# HEADERS_POWER.net
KiCad netlist of a schematic drawn in Altium Designer
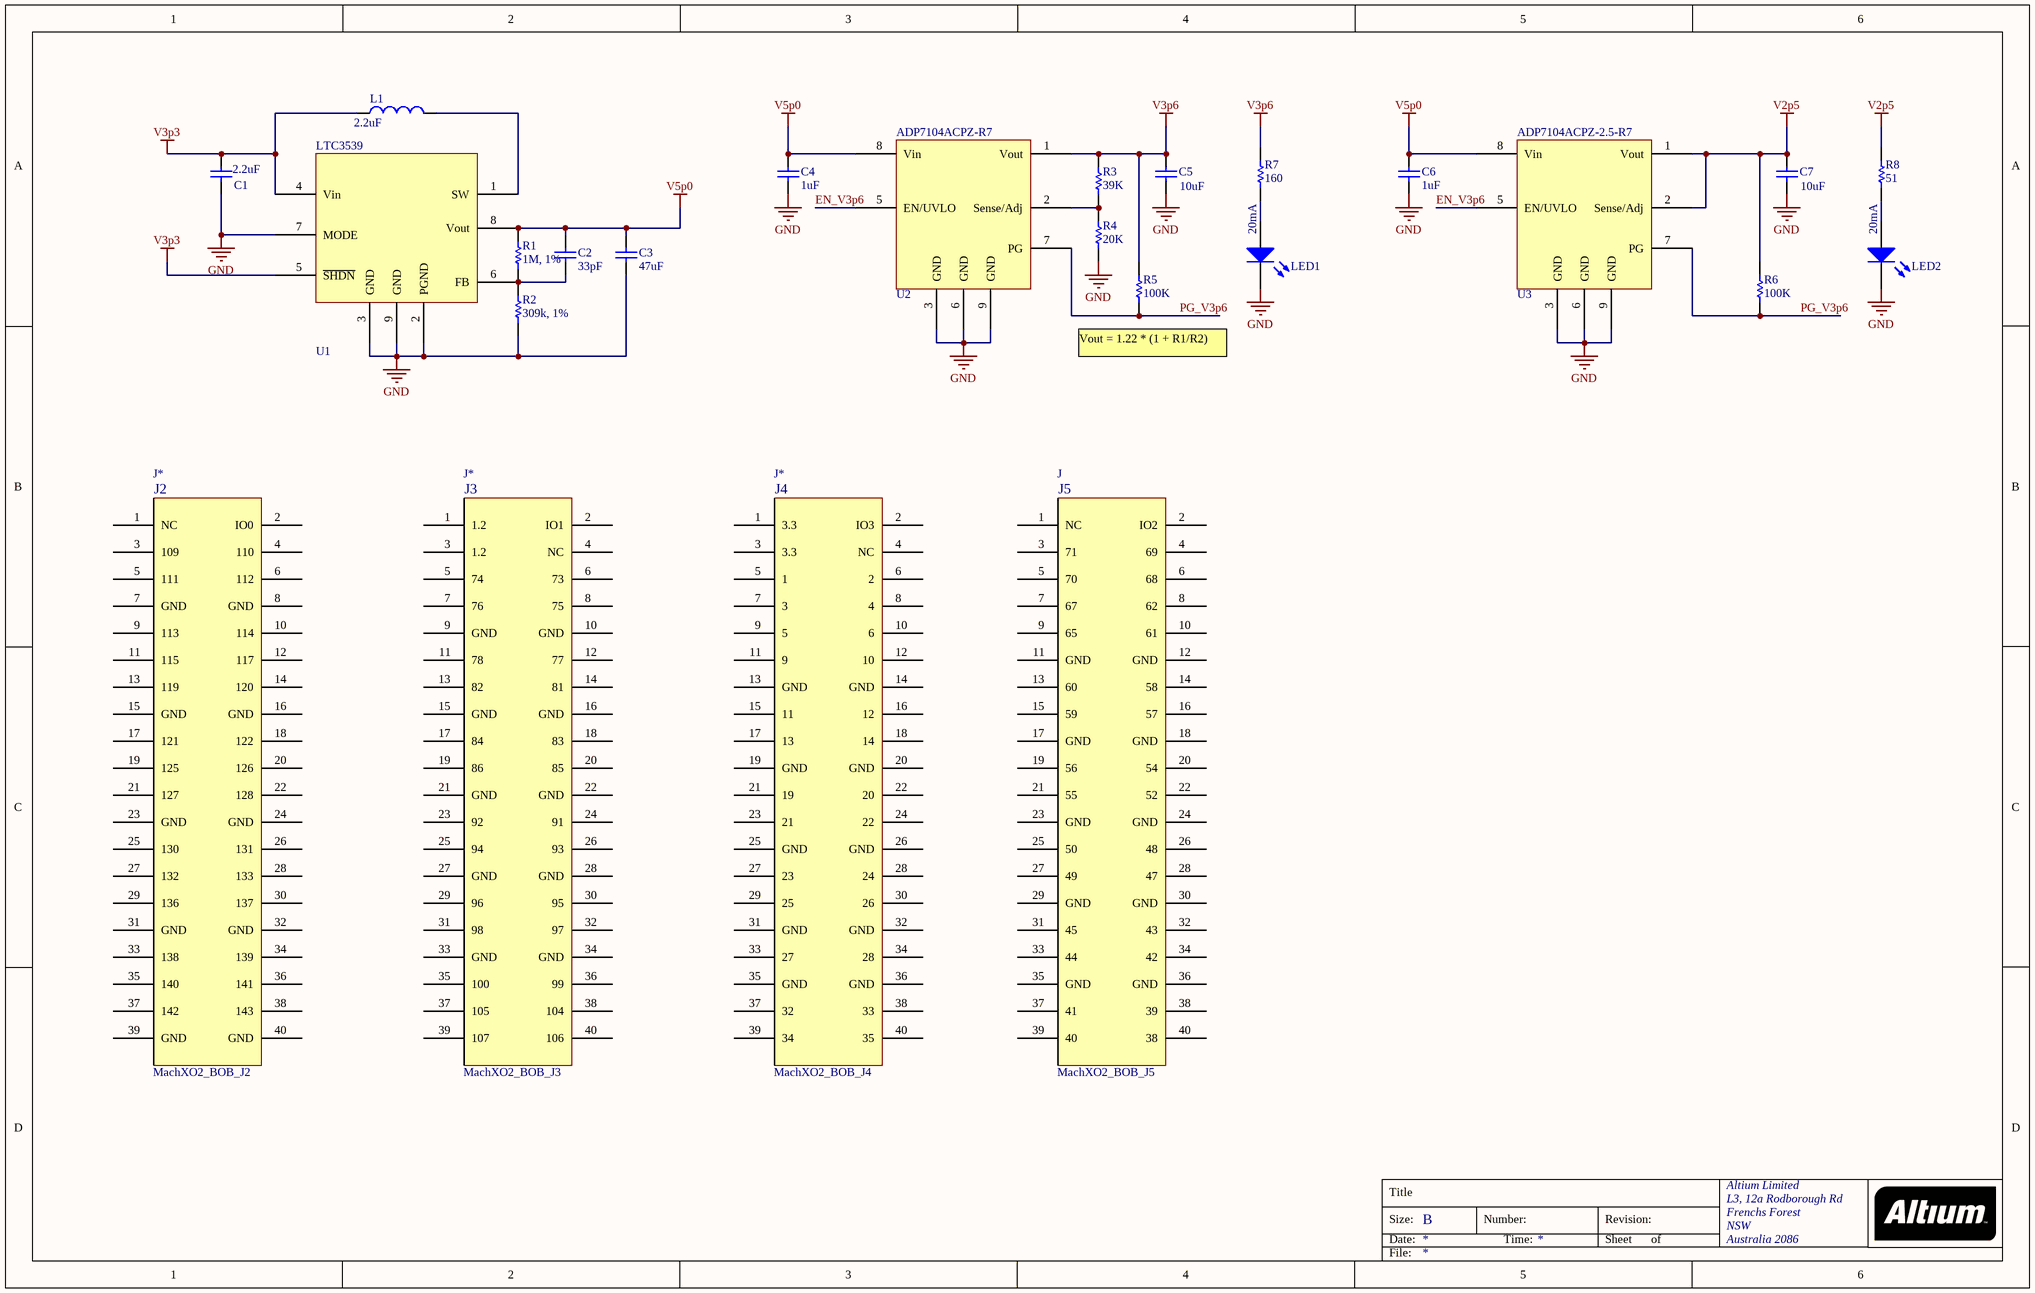
[diagram p0: HEADERS & POWER.SchDoc]

(export (version "E")
  (design (tool "Eeschema 10.0.6"))
  (components
    (comp (ref "C1")
      (value "2.2uF")
      (footprint "CAPC1206(3216)170_N")
      (fields (field (name "Comment") "587-1329-2-ND"))
      (libsource (lib "Components") (part "CAP, 1206, 2.2uF"))
    )
    (comp (ref "C2")
      (value "33pF")
      (footprint "CAPC01005(0402)22_N")
      (fields (field (name "Comment") "CAP, 0402, 33pF"))
      (libsource (lib "Components") (part "CAP, 0402, 33pF"))
    )
    (comp (ref "C3")
      (value "47uF")
      (footprint "CAPC1206(3216)170_N")
      (fields (field (name "Comment") "CAP, 1206, 47uF"))
      (libsource (lib "Components") (part "CAP, 1206, 47uF"))
    )
    (comp (ref "C4")
      (value "1uF")
      (footprint "CAPC01005(0402)22_N")
      (fields (field (name "Comment") "CAP, 0402, 1uF"))
      (libsource (lib "Components") (part "CAP, 0402, 1uF"))
    )
    (comp (ref "C5")
      (value "10uF")
      (footprint "CAPC0805(2012)130_N")
      (fields (field (name "Comment") "CAP, 0805, 10uF"))
      (libsource (lib "Components") (part "CAP, 0805, 10uF"))
    )
    (comp (ref "C6")
      (value "1uF")
      (footprint "CAPC01005(0402)22_N")
      (fields (field (name "Comment") "CAP, 0402, 1uF"))
      (libsource (lib "Components") (part "CAP, 0402, 1uF"))
    )
    (comp (ref "C7")
      (value "10uF")
      (footprint "CAPC0805(2012)130_N")
      (fields (field (name "Comment") "CAP, 0805, 10uF"))
      (libsource (lib "Components") (part "CAP, 0805, 10uF"))
    )
    (comp (ref "J")
      (value "MachXO2_BOB_J5")
      (footprint "RECEPTACLE_25.4MM_20X2")
      (libsource (lib "Components") (part "MachXO2_BOB_J5"))
    )
    (comp (ref "J*")
      (value "MachXO2_BOB_J2")
      (footprint "RECEPTACLE_25.4MM_20X2")
      (libsource (lib "Components") (part "MachXO2_BOB_J2"))
    )
    (comp (ref "L1")
      (value "2.2uF")
      (footprint "INDUCTOR, SMD, TDK")
      (fields (field (name "Comment") "INDUCTOR, SMD, 2.2uF"))
      (libsource (lib "Components") (part "INDUCTOR, SMD, 2.2uF"))
    )
    (comp (ref "LED1")
      (value "LED, GREEN, 0603, LITE-ON")
      (footprint "0603, LED")
      (libsource (lib "Components") (part "LED, GREEN, 0603, LITE-ON"))
    )
    (comp (ref "LED2")
      (value "LED, GREEN, 0603, LITE-ON")
      (footprint "0603, LED")
      (libsource (lib "Components") (part "LED, GREEN, 0603, LITE-ON"))
    )
    (comp (ref "R1")
      (value "1M, 1%")
      (footprint "RESC0402(1005)_N")
      (fields (field (name "Comment") "RES, 0402, 1M, 1%"))
      (libsource (lib "Components") (part "RES, 0402, 1M, 1%"))
    )
    (comp (ref "R2")
      (value "309k, 1%")
      (footprint "RESC0402(1005)_N")
      (fields (field (name "Comment") "RES, 0402, 309k, 1%"))
      (libsource (lib "Components") (part "RES, 0402, 309k, 1%"))
    )
    (comp (ref "R3")
      (value "39K")
      (footprint "RES, 0603")
      (description "Resistor, 0603, 1/10W, 39K ohm")
      (fields
        (field (name "MANUFACTURER") "Panasonic Electronic Components")
        (field (name "MANUFACTURER PART NUMBER") "ERJ-3EKF3902V")
      )
      (libsource (lib "Resistors0603") (part "RES_0603_39K"))
    )
    (comp (ref "R4")
      (value "20K")
      (footprint "RES, 0603")
      (description "Resistor, 0603, 1/10W, 20K ohm")
      (fields
        (field (name "MANUFACTURER") "Panasonic Electronic Components")
        (field (name "MANUFACTURER PART NUMBER") "ERJ-3EKF2002V")
      )
      (libsource (lib "Resistors0603") (part "RES_0603_20K"))
    )
    (comp (ref "R5")
      (value "100K")
      (footprint "RES, 0603")
      (description "Resistor, 0603, 1/10W, 100K ohm")
      (fields
        (field (name "MANUFACTURER") "Panasonic Electronic Components")
        (field (name "MANUFACTURER PART NUMBER") "ERJ-3EKF1003V")
      )
      (libsource (lib "Resistors0603") (part "RES_0603_100K"))
    )
    (comp (ref "R6")
      (value "100K")
      (footprint "RES, 0603")
      (description "Resistor, 0603, 1/10W, 100K ohm")
      (fields
        (field (name "MANUFACTURER") "Panasonic Electronic Components")
        (field (name "MANUFACTURER PART NUMBER") "ERJ-3EKF1003V")
      )
      (libsource (lib "Resistors0603") (part "RES_0603_100K"))
    )
    (comp (ref "R7")
      (value "160")
      (footprint "RESC1005X04N")
      (description "Resistor, 0402, 1/10W, 160 ohm")
      (fields
        (field (name "MANUFACTURER") "Panasonic Electronic Components")
        (field (name "MANUFACTURER PART NUMBER") "ERJ-2RKF1600X")
      )
      (libsource (lib "Resistors0402") (part "RES_0402_160"))
    )
    (comp (ref "R8")
      (value "51")
      (footprint "RESC1005X04N")
      (description "Resistor, 0402, 1/10W, 51 ohm")
      (fields
        (field (name "MANUFACTURER") "Panasonic Electronic Components")
        (field (name "MANUFACTURER PART NUMBER") "ERJ-2RKF51R0X")
      )
      (libsource (lib "Resistors0402") (part "RES_0402_51"))
    )
    (comp (ref "U1")
      (value "LTC3539")
      (footprint "QFN45P300X200X80-8N")
      (libsource (lib "Components") (part "LTC3539"))
    )
    (comp (ref "U2")
      (value "ADP7104ACPZ-R7")
      (footprint "QFN50P300X300X75-8N")
      (description "Adjustable Voltage Regulator")
      (libsource (lib "Components") (part "ADP7104ACPZ-R7"))
    )
    (comp (ref "U3")
      (value "ADP7104ACPZ-2.5-R7")
      (footprint "QFN50P300X300X75-8N")
      (description "2.5V Voltage Regulator")
      (libsource (lib "Components") (part "ADP7104ACPZ-2.5-R7"))
    )
  )
  (nets
    (net (code "1") (name "/EN_V3p6") (class "Default")
      (node (ref "U2") (pin "5") (pinfunction "EN/UVLO_5") (pintype "passive"))
      (node (ref "U3") (pin "5") (pinfunction "EN/UVLO_5") (pintype "passive"))
    )
    (net (code "2") (name "/PG_V3p6") (class "Default")
      (node (ref "R5") (pin "1") (pinfunction "1_1") (pintype "passive"))
      (node (ref "R6") (pin "1") (pinfunction "1_1") (pintype "passive"))
      (node (ref "U2") (pin "7") (pinfunction "PG_7") (pintype "passive"))
      (node (ref "U3") (pin "7") (pinfunction "PG_7") (pintype "passive"))
    )
    (net (code "3") (name "GND") (class "Default")
      (node (ref "C1") (pin "1") (pinfunction "1_1") (pintype "passive"))
      (node (ref "C3") (pin "1") (pinfunction "1_1") (pintype "passive"))
      (node (ref "C4") (pin "1") (pinfunction "1_1") (pintype "passive"))
      (node (ref "C5") (pin "1") (pinfunction "1_1") (pintype "passive"))
      (node (ref "C6") (pin "1") (pinfunction "1_1") (pintype "passive"))
      (node (ref "C7") (pin "1") (pinfunction "1_1") (pintype "passive"))
      (node (ref "LED1") (pin "1") (pinfunction "C_1") (pintype "passive"))
      (node (ref "LED2") (pin "1") (pinfunction "C_1") (pintype "passive"))
      (node (ref "R2") (pin "1") (pinfunction "1_1") (pintype "passive"))
      (node (ref "R4") (pin "1") (pinfunction "1_1") (pintype "passive"))
      (node (ref "U1") (pin "2") (pinfunction "PGND_2") (pintype "passive"))
      (node (ref "U1") (pin "3") (pinfunction "GND_3") (pintype "passive"))
      (node (ref "U1") (pin "7") (pinfunction "MODE_7") (pintype "passive"))
      (node (ref "U1") (pin "9") (pinfunction "GND_9") (pintype "passive"))
      (node (ref "U2") (pin "3") (pinfunction "GND_3") (pintype "passive"))
      (node (ref "U2") (pin "6") (pinfunction "GND_6") (pintype "passive"))
      (node (ref "U2") (pin "9") (pinfunction "GND_9") (pintype "passive"))
      (node (ref "U3") (pin "3") (pinfunction "GND_3") (pintype "passive"))
      (node (ref "U3") (pin "6") (pinfunction "GND_6") (pintype "passive"))
      (node (ref "U3") (pin "9") (pinfunction "GND_9") (pintype "passive"))
    )
    (net (code "4") (name "Net-(LED1-A)") (class "Default")
      (node (ref "LED1") (pin "2") (pinfunction "A_2") (pintype "passive"))
      (node (ref "R7") (pin "1") (pinfunction "1_1") (pintype "passive"))
    )
    (net (code "5") (name "Net-(LED2-A)") (class "Default")
      (node (ref "LED2") (pin "2") (pinfunction "A_2") (pintype "passive"))
      (node (ref "R8") (pin "1") (pinfunction "1_1") (pintype "passive"))
    )
    (net (code "6") (name "Net-(U1-FB)") (class "Default")
      (node (ref "C2") (pin "1") (pinfunction "1_1") (pintype "passive"))
      (node (ref "R1") (pin "1") (pinfunction "1_1") (pintype "passive"))
      (node (ref "R2") (pin "2") (pinfunction "2_2") (pintype "passive"))
      (node (ref "U1") (pin "6") (pinfunction "FB_6") (pintype "passive"))
    )
    (net (code "7") (name "Net-(U1-SW)") (class "Default")
      (node (ref "L1") (pin "2") (pinfunction "2_2") (pintype "passive"))
      (node (ref "U1") (pin "1") (pinfunction "SW_1") (pintype "passive"))
    )
    (net (code "8") (name "Net-(U2-Sense{slash}Adj)") (class "Default")
      (node (ref "R3") (pin "1") (pinfunction "1_1") (pintype "passive"))
      (node (ref "R4") (pin "2") (pinfunction "2_2") (pintype "passive"))
      (node (ref "U2") (pin "2") (pinfunction "Sense/Adj_2") (pintype "passive"))
    )
    (net (code "9") (name "V2p5") (class "Default")
      (node (ref "C7") (pin "2") (pinfunction "2_2") (pintype "passive"))
      (node (ref "R6") (pin "2") (pinfunction "2_2") (pintype "passive"))
      (node (ref "R8") (pin "2") (pinfunction "2_2") (pintype "passive"))
      (node (ref "U3") (pin "1") (pinfunction "Vout_1") (pintype "passive"))
      (node (ref "U3") (pin "2") (pinfunction "Sense/Adj_2") (pintype "passive"))
    )
    (net (code "10") (name "V3p3") (class "Default")
      (node (ref "C1") (pin "2") (pinfunction "2_2") (pintype "passive"))
      (node (ref "L1") (pin "1") (pinfunction "1_1") (pintype "passive"))
      (node (ref "U1") (pin "4") (pinfunction "Vin_4") (pintype "passive"))
      (node (ref "U1") (pin "5") (pinfunction "~{SHDN}_5") (pintype "passive"))
    )
    (net (code "11") (name "V3p6") (class "Default")
      (node (ref "C5") (pin "2") (pinfunction "2_2") (pintype "passive"))
      (node (ref "R3") (pin "2") (pinfunction "2_2") (pintype "passive"))
      (node (ref "R5") (pin "2") (pinfunction "2_2") (pintype "passive"))
      (node (ref "R7") (pin "2") (pinfunction "2_2") (pintype "passive"))
      (node (ref "U2") (pin "1") (pinfunction "Vout_1") (pintype "passive"))
    )
    (net (code "12") (name "V5p0") (class "Default")
      (node (ref "C2") (pin "2") (pinfunction "2_2") (pintype "passive"))
      (node (ref "C3") (pin "2") (pinfunction "2_2") (pintype "passive"))
      (node (ref "C4") (pin "2") (pinfunction "2_2") (pintype "passive"))
      (node (ref "C6") (pin "2") (pinfunction "2_2") (pintype "passive"))
      (node (ref "R1") (pin "2") (pinfunction "2_2") (pintype "passive"))
      (node (ref "U1") (pin "8") (pinfunction "Vout_8") (pintype "passive"))
      (node (ref "U2") (pin "8") (pinfunction "Vin_8") (pintype "passive"))
      (node (ref "U3") (pin "8") (pinfunction "Vin_8") (pintype "passive"))
    )
    (net (code "13") (name "unconnected-(J*-1-Pad5)") (class "Default")
      (node (ref "J*") (pin "5") (pinfunction "1_5") (pintype "passive"))
    )
    (net (code "14") (name "unconnected-(J*-1.2-Pad1)") (class "Default")
      (node (ref "J*") (pin "1") (pinfunction "1.2_1") (pintype "passive"))
    )
    (net (code "15") (name "unconnected-(J*-1.2-Pad3)") (class "Default")
      (node (ref "J*") (pin "3") (pinfunction "1.2_3") (pintype "passive"))
    )
    (net (code "16") (name "unconnected-(J*-2-Pad6)") (class "Default")
      (node (ref "J*") (pin "6") (pinfunction "2_6") (pintype "passive"))
    )
    (net (code "17") (name "unconnected-(J*-3-Pad7)") (class "Default")
      (node (ref "J*") (pin "7") (pinfunction "3_7") (pintype "passive"))
    )
    (net (code "18") (name "unconnected-(J*-3.3-Pad1)") (class "Default")
      (node (ref "J*") (pin "1") (pinfunction "3.3_1") (pintype "passive"))
    )
    (net (code "19") (name "unconnected-(J*-3.3-Pad3)") (class "Default")
      (node (ref "J*") (pin "3") (pinfunction "3.3_3") (pintype "passive"))
    )
    (net (code "20") (name "unconnected-(J*-4-Pad8)") (class "Default")
      (node (ref "J*") (pin "8") (pinfunction "4_8") (pintype "passive"))
    )
    (net (code "21") (name "unconnected-(J*-5-Pad9)") (class "Default")
      (node (ref "J*") (pin "9") (pinfunction "5_9") (pintype "passive"))
    )
    (net (code "22") (name "unconnected-(J*-6-Pad10)") (class "Default")
      (node (ref "J*") (pin "10") (pinfunction "6_10") (pintype "passive"))
    )
    (net (code "23") (name "unconnected-(J*-9-Pad11)") (class "Default")
      (node (ref "J*") (pin "11") (pinfunction "9_11") (pintype "passive"))
    )
    (net (code "24") (name "unconnected-(J*-10-Pad12)") (class "Default")
      (node (ref "J*") (pin "12") (pinfunction "10_12") (pintype "passive"))
    )
    (net (code "25") (name "unconnected-(J*-11-Pad15)") (class "Default")
      (node (ref "J*") (pin "15") (pinfunction "11_15") (pintype "passive"))
    )
    (net (code "26") (name "unconnected-(J*-12-Pad16)") (class "Default")
      (node (ref "J*") (pin "16") (pinfunction "12_16") (pintype "passive"))
    )
    (net (code "27") (name "unconnected-(J*-13-Pad17)") (class "Default")
      (node (ref "J*") (pin "17") (pinfunction "13_17") (pintype "passive"))
    )
    (net (code "28") (name "unconnected-(J*-14-Pad18)") (class "Default")
      (node (ref "J*") (pin "18") (pinfunction "14_18") (pintype "passive"))
    )
    (net (code "29") (name "unconnected-(J*-19-Pad21)") (class "Default")
      (node (ref "J*") (pin "21") (pinfunction "19_21") (pintype "passive"))
    )
    (net (code "30") (name "unconnected-(J*-20-Pad22)") (class "Default")
      (node (ref "J*") (pin "22") (pinfunction "20_22") (pintype "passive"))
    )
    (net (code "31") (name "unconnected-(J*-21-Pad23)") (class "Default")
      (node (ref "J*") (pin "23") (pinfunction "21_23") (pintype "passive"))
    )
    (net (code "32") (name "unconnected-(J*-22-Pad24)") (class "Default")
      (node (ref "J*") (pin "24") (pinfunction "22_24") (pintype "passive"))
    )
    (net (code "33") (name "unconnected-(J*-23-Pad27)") (class "Default")
      (node (ref "J*") (pin "27") (pinfunction "23_27") (pintype "passive"))
    )
    (net (code "34") (name "unconnected-(J*-24-Pad28)") (class "Default")
      (node (ref "J*") (pin "28") (pinfunction "24_28") (pintype "passive"))
    )
    (net (code "35") (name "unconnected-(J*-25-Pad29)") (class "Default")
      (node (ref "J*") (pin "29") (pinfunction "25_29") (pintype "passive"))
    )
    (net (code "36") (name "unconnected-(J*-26-Pad30)") (class "Default")
      (node (ref "J*") (pin "30") (pinfunction "26_30") (pintype "passive"))
    )
    (net (code "37") (name "unconnected-(J*-27-Pad33)") (class "Default")
      (node (ref "J*") (pin "33") (pinfunction "27_33") (pintype "passive"))
    )
    (net (code "38") (name "unconnected-(J*-28-Pad34)") (class "Default")
      (node (ref "J*") (pin "34") (pinfunction "28_34") (pintype "passive"))
    )
    (net (code "39") (name "unconnected-(J*-32-Pad37)") (class "Default")
      (node (ref "J*") (pin "37") (pinfunction "32_37") (pintype "passive"))
    )
    (net (code "40") (name "unconnected-(J*-33-Pad38)") (class "Default")
      (node (ref "J*") (pin "38") (pinfunction "33_38") (pintype "passive"))
    )
    (net (code "41") (name "unconnected-(J*-34-Pad39)") (class "Default")
      (node (ref "J*") (pin "39") (pinfunction "34_39") (pintype "passive"))
    )
    (net (code "42") (name "unconnected-(J*-35-Pad40)") (class "Default")
      (node (ref "J*") (pin "40") (pinfunction "35_40") (pintype "passive"))
    )
    (net (code "43") (name "unconnected-(J*-73-Pad6)") (class "Default")
      (node (ref "J*") (pin "6") (pinfunction "73_6") (pintype "passive"))
    )
    (net (code "44") (name "unconnected-(J*-74-Pad5)") (class "Default")
      (node (ref "J*") (pin "5") (pinfunction "74_5") (pintype "passive"))
    )
    (net (code "45") (name "unconnected-(J*-75-Pad8)") (class "Default")
      (node (ref "J*") (pin "8") (pinfunction "75_8") (pintype "passive"))
    )
    (net (code "46") (name "unconnected-(J*-76-Pad7)") (class "Default")
      (node (ref "J*") (pin "7") (pinfunction "76_7") (pintype "passive"))
    )
    (net (code "47") (name "unconnected-(J*-77-Pad12)") (class "Default")
      (node (ref "J*") (pin "12") (pinfunction "77_12") (pintype "passive"))
    )
    (net (code "48") (name "unconnected-(J*-78-Pad11)") (class "Default")
      (node (ref "J*") (pin "11") (pinfunction "78_11") (pintype "passive"))
    )
    (net (code "49") (name "unconnected-(J*-81-Pad14)") (class "Default")
      (node (ref "J*") (pin "14") (pinfunction "81_14") (pintype "passive"))
    )
    (net (code "50") (name "unconnected-(J*-82-Pad13)") (class "Default")
      (node (ref "J*") (pin "13") (pinfunction "82_13") (pintype "passive"))
    )
    (net (code "51") (name "unconnected-(J*-83-Pad18)") (class "Default")
      (node (ref "J*") (pin "18") (pinfunction "83_18") (pintype "passive"))
    )
    (net (code "52") (name "unconnected-(J*-84-Pad17)") (class "Default")
      (node (ref "J*") (pin "17") (pinfunction "84_17") (pintype "passive"))
    )
    (net (code "53") (name "unconnected-(J*-85-Pad20)") (class "Default")
      (node (ref "J*") (pin "20") (pinfunction "85_20") (pintype "passive"))
    )
    (net (code "54") (name "unconnected-(J*-86-Pad19)") (class "Default")
      (node (ref "J*") (pin "19") (pinfunction "86_19") (pintype "passive"))
    )
    (net (code "55") (name "unconnected-(J*-91-Pad24)") (class "Default")
      (node (ref "J*") (pin "24") (pinfunction "91_24") (pintype "passive"))
    )
    (net (code "56") (name "unconnected-(J*-92-Pad23)") (class "Default")
      (node (ref "J*") (pin "23") (pinfunction "92_23") (pintype "passive"))
    )
    (net (code "57") (name "unconnected-(J*-93-Pad26)") (class "Default")
      (node (ref "J*") (pin "26") (pinfunction "93_26") (pintype "passive"))
    )
    (net (code "58") (name "unconnected-(J*-94-Pad25)") (class "Default")
      (node (ref "J*") (pin "25") (pinfunction "94_25") (pintype "passive"))
    )
    (net (code "59") (name "unconnected-(J*-95-Pad30)") (class "Default")
      (node (ref "J*") (pin "30") (pinfunction "95_30") (pintype "passive"))
    )
    (net (code "60") (name "unconnected-(J*-96-Pad29)") (class "Default")
      (node (ref "J*") (pin "29") (pinfunction "96_29") (pintype "passive"))
    )
    (net (code "61") (name "unconnected-(J*-97-Pad32)") (class "Default")
      (node (ref "J*") (pin "32") (pinfunction "97_32") (pintype "passive"))
    )
    (net (code "62") (name "unconnected-(J*-98-Pad31)") (class "Default")
      (node (ref "J*") (pin "31") (pinfunction "98_31") (pintype "passive"))
    )
    (net (code "63") (name "unconnected-(J*-99-Pad36)") (class "Default")
      (node (ref "J*") (pin "36") (pinfunction "99_36") (pintype "passive"))
    )
    (net (code "64") (name "unconnected-(J*-100-Pad35)") (class "Default")
      (node (ref "J*") (pin "35") (pinfunction "100_35") (pintype "passive"))
    )
    (net (code "65") (name "unconnected-(J*-104-Pad38)") (class "Default")
      (node (ref "J*") (pin "38") (pinfunction "104_38") (pintype "passive"))
    )
    (net (code "66") (name "unconnected-(J*-105-Pad37)") (class "Default")
      (node (ref "J*") (pin "37") (pinfunction "105_37") (pintype "passive"))
    )
    (net (code "67") (name "unconnected-(J*-106-Pad40)") (class "Default")
      (node (ref "J*") (pin "40") (pinfunction "106_40") (pintype "passive"))
    )
    (net (code "68") (name "unconnected-(J*-107-Pad39)") (class "Default")
      (node (ref "J*") (pin "39") (pinfunction "107_39") (pintype "passive"))
    )
    (net (code "69") (name "unconnected-(J*-109-Pad3)") (class "Default")
      (node (ref "J*") (pin "3") (pinfunction "109_3") (pintype "passive"))
    )
    (net (code "70") (name "unconnected-(J*-110-Pad4)") (class "Default")
      (node (ref "J*") (pin "4") (pinfunction "110_4") (pintype "passive"))
    )
    (net (code "71") (name "unconnected-(J*-111-Pad5)") (class "Default")
      (node (ref "J*") (pin "5") (pinfunction "111_5") (pintype "passive"))
    )
    (net (code "72") (name "unconnected-(J*-112-Pad6)") (class "Default")
      (node (ref "J*") (pin "6") (pinfunction "112_6") (pintype "passive"))
    )
    (net (code "73") (name "unconnected-(J*-113-Pad9)") (class "Default")
      (node (ref "J*") (pin "9") (pinfunction "113_9") (pintype "passive"))
    )
    (net (code "74") (name "unconnected-(J*-114-Pad10)") (class "Default")
      (node (ref "J*") (pin "10") (pinfunction "114_10") (pintype "passive"))
    )
    (net (code "75") (name "unconnected-(J*-115-Pad11)") (class "Default")
      (node (ref "J*") (pin "11") (pinfunction "115_11") (pintype "passive"))
    )
    (net (code "76") (name "unconnected-(J*-117-Pad12)") (class "Default")
      (node (ref "J*") (pin "12") (pinfunction "117_12") (pintype "passive"))
    )
    (net (code "77") (name "unconnected-(J*-119-Pad13)") (class "Default")
      (node (ref "J*") (pin "13") (pinfunction "119_13") (pintype "passive"))
    )
    (net (code "78") (name "unconnected-(J*-120-Pad14)") (class "Default")
      (node (ref "J*") (pin "14") (pinfunction "120_14") (pintype "passive"))
    )
    (net (code "79") (name "unconnected-(J*-121-Pad17)") (class "Default")
      (node (ref "J*") (pin "17") (pinfunction "121_17") (pintype "passive"))
    )
    (net (code "80") (name "unconnected-(J*-122-Pad18)") (class "Default")
      (node (ref "J*") (pin "18") (pinfunction "122_18") (pintype "passive"))
    )
    (net (code "81") (name "unconnected-(J*-125-Pad19)") (class "Default")
      (node (ref "J*") (pin "19") (pinfunction "125_19") (pintype "passive"))
    )
    (net (code "82") (name "unconnected-(J*-126-Pad20)") (class "Default")
      (node (ref "J*") (pin "20") (pinfunction "126_20") (pintype "passive"))
    )
    (net (code "83") (name "unconnected-(J*-127-Pad21)") (class "Default")
      (node (ref "J*") (pin "21") (pinfunction "127_21") (pintype "passive"))
    )
    (net (code "84") (name "unconnected-(J*-128-Pad22)") (class "Default")
      (node (ref "J*") (pin "22") (pinfunction "128_22") (pintype "passive"))
    )
    (net (code "85") (name "unconnected-(J*-130-Pad25)") (class "Default")
      (node (ref "J*") (pin "25") (pinfunction "130_25") (pintype "passive"))
    )
    (net (code "86") (name "unconnected-(J*-131-Pad26)") (class "Default")
      (node (ref "J*") (pin "26") (pinfunction "131_26") (pintype "passive"))
    )
    (net (code "87") (name "unconnected-(J*-132-Pad27)") (class "Default")
      (node (ref "J*") (pin "27") (pinfunction "132_27") (pintype "passive"))
    )
    (net (code "88") (name "unconnected-(J*-133-Pad28)") (class "Default")
      (node (ref "J*") (pin "28") (pinfunction "133_28") (pintype "passive"))
    )
    (net (code "89") (name "unconnected-(J*-136-Pad29)") (class "Default")
      (node (ref "J*") (pin "29") (pinfunction "136_29") (pintype "passive"))
    )
    (net (code "90") (name "unconnected-(J*-137-Pad30)") (class "Default")
      (node (ref "J*") (pin "30") (pinfunction "137_30") (pintype "passive"))
    )
    (net (code "91") (name "unconnected-(J*-138-Pad33)") (class "Default")
      (node (ref "J*") (pin "33") (pinfunction "138_33") (pintype "passive"))
    )
    (net (code "92") (name "unconnected-(J*-139-Pad34)") (class "Default")
      (node (ref "J*") (pin "34") (pinfunction "139_34") (pintype "passive"))
    )
    (net (code "93") (name "unconnected-(J*-140-Pad35)") (class "Default")
      (node (ref "J*") (pin "35") (pinfunction "140_35") (pintype "passive"))
    )
    (net (code "94") (name "unconnected-(J*-141-Pad36)") (class "Default")
      (node (ref "J*") (pin "36") (pinfunction "141_36") (pintype "passive"))
    )
    (net (code "95") (name "unconnected-(J*-142-Pad37)") (class "Default")
      (node (ref "J*") (pin "37") (pinfunction "142_37") (pintype "passive"))
    )
    (net (code "96") (name "unconnected-(J*-143-Pad38)") (class "Default")
      (node (ref "J*") (pin "38") (pinfunction "143_38") (pintype "passive"))
    )
    (net (code "97") (name "unconnected-(J*-GND-Pad7)") (class "Default")
      (node (ref "J*") (pin "7") (pinfunction "GND_7") (pintype "passive"))
    )
    (net (code "98") (name "unconnected-(J*-GND-Pad8)") (class "Default")
      (node (ref "J*") (pin "8") (pinfunction "GND_8") (pintype "passive"))
    )
    (net (code "99") (name "unconnected-(J*-GND-Pad9)") (class "Default")
      (node (ref "J*") (pin "9") (pinfunction "GND_9") (pintype "passive"))
    )
    (net (code "100") (name "unconnected-(J*-GND-Pad10)") (class "Default")
      (node (ref "J*") (pin "10") (pinfunction "GND_10") (pintype "passive"))
    )
    (net (code "101") (name "unconnected-(J*-GND-Pad13)") (class "Default")
      (node (ref "J*") (pin "13") (pinfunction "GND_13") (pintype "passive"))
    )
    (net (code "102") (name "unconnected-(J*-GND-Pad14)") (class "Default")
      (node (ref "J*") (pin "14") (pinfunction "GND_14") (pintype "passive"))
    )
    (net (code "103") (name "unconnected-(J*-GND-Pad15)") (class "Default")
      (node (ref "J*") (pin "15") (pinfunction "GND_15") (pintype "passive"))
    )
    (net (code "104") (name "unconnected-(J*-GND-Pad15)_1") (class "Default")
      (node (ref "J*") (pin "15") (pinfunction "GND_15") (pintype "passive"))
    )
    (net (code "105") (name "unconnected-(J*-GND-Pad16)") (class "Default")
      (node (ref "J*") (pin "16") (pinfunction "GND_16") (pintype "passive"))
    )
    (net (code "106") (name "unconnected-(J*-GND-Pad16)_1") (class "Default")
      (node (ref "J*") (pin "16") (pinfunction "GND_16") (pintype "passive"))
    )
    (net (code "107") (name "unconnected-(J*-GND-Pad19)") (class "Default")
      (node (ref "J*") (pin "19") (pinfunction "GND_19") (pintype "passive"))
    )
    (net (code "108") (name "unconnected-(J*-GND-Pad20)") (class "Default")
      (node (ref "J*") (pin "20") (pinfunction "GND_20") (pintype "passive"))
    )
    (net (code "109") (name "unconnected-(J*-GND-Pad21)") (class "Default")
      (node (ref "J*") (pin "21") (pinfunction "GND_21") (pintype "passive"))
    )
    (net (code "110") (name "unconnected-(J*-GND-Pad22)") (class "Default")
      (node (ref "J*") (pin "22") (pinfunction "GND_22") (pintype "passive"))
    )
    (net (code "111") (name "unconnected-(J*-GND-Pad23)") (class "Default")
      (node (ref "J*") (pin "23") (pinfunction "GND_23") (pintype "passive"))
    )
    (net (code "112") (name "unconnected-(J*-GND-Pad24)") (class "Default")
      (node (ref "J*") (pin "24") (pinfunction "GND_24") (pintype "passive"))
    )
    (net (code "113") (name "unconnected-(J*-GND-Pad25)") (class "Default")
      (node (ref "J*") (pin "25") (pinfunction "GND_25") (pintype "passive"))
    )
    (net (code "114") (name "unconnected-(J*-GND-Pad26)") (class "Default")
      (node (ref "J*") (pin "26") (pinfunction "GND_26") (pintype "passive"))
    )
    (net (code "115") (name "unconnected-(J*-GND-Pad27)") (class "Default")
      (node (ref "J*") (pin "27") (pinfunction "GND_27") (pintype "passive"))
    )
    (net (code "116") (name "unconnected-(J*-GND-Pad28)") (class "Default")
      (node (ref "J*") (pin "28") (pinfunction "GND_28") (pintype "passive"))
    )
    (net (code "117") (name "unconnected-(J*-GND-Pad31)") (class "Default")
      (node (ref "J*") (pin "31") (pinfunction "GND_31") (pintype "passive"))
    )
    (net (code "118") (name "unconnected-(J*-GND-Pad31)_1") (class "Default")
      (node (ref "J*") (pin "31") (pinfunction "GND_31") (pintype "passive"))
    )
    (net (code "119") (name "unconnected-(J*-GND-Pad32)") (class "Default")
      (node (ref "J*") (pin "32") (pinfunction "GND_32") (pintype "passive"))
    )
    (net (code "120") (name "unconnected-(J*-GND-Pad32)_1") (class "Default")
      (node (ref "J*") (pin "32") (pinfunction "GND_32") (pintype "passive"))
    )
    (net (code "121") (name "unconnected-(J*-GND-Pad33)") (class "Default")
      (node (ref "J*") (pin "33") (pinfunction "GND_33") (pintype "passive"))
    )
    (net (code "122") (name "unconnected-(J*-GND-Pad34)") (class "Default")
      (node (ref "J*") (pin "34") (pinfunction "GND_34") (pintype "passive"))
    )
    (net (code "123") (name "unconnected-(J*-GND-Pad35)") (class "Default")
      (node (ref "J*") (pin "35") (pinfunction "GND_35") (pintype "passive"))
    )
    (net (code "124") (name "unconnected-(J*-GND-Pad36)") (class "Default")
      (node (ref "J*") (pin "36") (pinfunction "GND_36") (pintype "passive"))
    )
    (net (code "125") (name "unconnected-(J*-GND-Pad39)") (class "Default")
      (node (ref "J*") (pin "39") (pinfunction "GND_39") (pintype "passive"))
    )
    (net (code "126") (name "unconnected-(J*-GND-Pad40)") (class "Default")
      (node (ref "J*") (pin "40") (pinfunction "GND_40") (pintype "passive"))
    )
    (net (code "127") (name "unconnected-(J*-IO0-Pad2)") (class "Default")
      (node (ref "J*") (pin "2") (pinfunction "IO0_2") (pintype "passive"))
    )
    (net (code "128") (name "unconnected-(J*-IO1-Pad2)") (class "Default")
      (node (ref "J*") (pin "2") (pinfunction "IO1_2") (pintype "passive"))
    )
    (net (code "129") (name "unconnected-(J*-IO3-Pad2)") (class "Default")
      (node (ref "J*") (pin "2") (pinfunction "IO3_2") (pintype "passive"))
    )
    (net (code "130") (name "unconnected-(J*-NC-Pad1)_2") (class "Default")
      (node (ref "J*") (pin "1") (pinfunction "NC_1") (pintype "passive"))
    )
    (net (code "131") (name "unconnected-(J*-NC-Pad4)") (class "Default")
      (node (ref "J*") (pin "4") (pinfunction "NC_4") (pintype "passive"))
    )
    (net (code "132") (name "unconnected-(J*-NC-Pad4)_1") (class "Default")
      (node (ref "J*") (pin "4") (pinfunction "NC_4") (pintype "passive"))
    )
    (net (code "133") (name "unconnected-(J-38-Pad40)") (class "Default")
      (node (ref "J") (pin "40") (pinfunction "38_40") (pintype "passive"))
    )
    (net (code "134") (name "unconnected-(J-39-Pad38)") (class "Default")
      (node (ref "J") (pin "38") (pinfunction "39_38") (pintype "passive"))
    )
    (net (code "135") (name "unconnected-(J-40-Pad39)") (class "Default")
      (node (ref "J") (pin "39") (pinfunction "40_39") (pintype "passive"))
    )
    (net (code "136") (name "unconnected-(J-41-Pad37)") (class "Default")
      (node (ref "J") (pin "37") (pinfunction "41_37") (pintype "passive"))
    )
    (net (code "137") (name "unconnected-(J-42-Pad34)") (class "Default")
      (node (ref "J") (pin "34") (pinfunction "42_34") (pintype "passive"))
    )
    (net (code "138") (name "unconnected-(J-43-Pad32)") (class "Default")
      (node (ref "J") (pin "32") (pinfunction "43_32") (pintype "passive"))
    )
    (net (code "139") (name "unconnected-(J-44-Pad33)") (class "Default")
      (node (ref "J") (pin "33") (pinfunction "44_33") (pintype "passive"))
    )
    (net (code "140") (name "unconnected-(J-45-Pad31)") (class "Default")
      (node (ref "J") (pin "31") (pinfunction "45_31") (pintype "passive"))
    )
    (net (code "141") (name "unconnected-(J-47-Pad28)") (class "Default")
      (node (ref "J") (pin "28") (pinfunction "47_28") (pintype "passive"))
    )
    (net (code "142") (name "unconnected-(J-48-Pad26)") (class "Default")
      (node (ref "J") (pin "26") (pinfunction "48_26") (pintype "passive"))
    )
    (net (code "143") (name "unconnected-(J-49-Pad27)") (class "Default")
      (node (ref "J") (pin "27") (pinfunction "49_27") (pintype "passive"))
    )
    (net (code "144") (name "unconnected-(J-50-Pad25)") (class "Default")
      (node (ref "J") (pin "25") (pinfunction "50_25") (pintype "passive"))
    )
    (net (code "145") (name "unconnected-(J-52-Pad22)") (class "Default")
      (node (ref "J") (pin "22") (pinfunction "52_22") (pintype "passive"))
    )
    (net (code "146") (name "unconnected-(J-54-Pad20)") (class "Default")
      (node (ref "J") (pin "20") (pinfunction "54_20") (pintype "passive"))
    )
    (net (code "147") (name "unconnected-(J-55-Pad21)") (class "Default")
      (node (ref "J") (pin "21") (pinfunction "55_21") (pintype "passive"))
    )
    (net (code "148") (name "unconnected-(J-56-Pad19)") (class "Default")
      (node (ref "J") (pin "19") (pinfunction "56_19") (pintype "passive"))
    )
    (net (code "149") (name "unconnected-(J-57-Pad16)") (class "Default")
      (node (ref "J") (pin "16") (pinfunction "57_16") (pintype "passive"))
    )
    (net (code "150") (name "unconnected-(J-58-Pad14)") (class "Default")
      (node (ref "J") (pin "14") (pinfunction "58_14") (pintype "passive"))
    )
    (net (code "151") (name "unconnected-(J-59-Pad15)") (class "Default")
      (node (ref "J") (pin "15") (pinfunction "59_15") (pintype "passive"))
    )
    (net (code "152") (name "unconnected-(J-60-Pad13)") (class "Default")
      (node (ref "J") (pin "13") (pinfunction "60_13") (pintype "passive"))
    )
    (net (code "153") (name "unconnected-(J-61-Pad10)") (class "Default")
      (node (ref "J") (pin "10") (pinfunction "61_10") (pintype "passive"))
    )
    (net (code "154") (name "unconnected-(J-62-Pad8)") (class "Default")
      (node (ref "J") (pin "8") (pinfunction "62_8") (pintype "passive"))
    )
    (net (code "155") (name "unconnected-(J-65-Pad9)") (class "Default")
      (node (ref "J") (pin "9") (pinfunction "65_9") (pintype "passive"))
    )
    (net (code "156") (name "unconnected-(J-67-Pad7)") (class "Default")
      (node (ref "J") (pin "7") (pinfunction "67_7") (pintype "passive"))
    )
    (net (code "157") (name "unconnected-(J-68-Pad6)") (class "Default")
      (node (ref "J") (pin "6") (pinfunction "68_6") (pintype "passive"))
    )
    (net (code "158") (name "unconnected-(J-69-Pad4)") (class "Default")
      (node (ref "J") (pin "4") (pinfunction "69_4") (pintype "passive"))
    )
    (net (code "159") (name "unconnected-(J-70-Pad5)") (class "Default")
      (node (ref "J") (pin "5") (pinfunction "70_5") (pintype "passive"))
    )
    (net (code "160") (name "unconnected-(J-71-Pad3)") (class "Default")
      (node (ref "J") (pin "3") (pinfunction "71_3") (pintype "passive"))
    )
    (net (code "161") (name "unconnected-(J-GND-Pad11)") (class "Default")
      (node (ref "J") (pin "11") (pinfunction "GND_11") (pintype "passive"))
    )
    (net (code "162") (name "unconnected-(J-GND-Pad12)") (class "Default")
      (node (ref "J") (pin "12") (pinfunction "GND_12") (pintype "passive"))
    )
    (net (code "163") (name "unconnected-(J-GND-Pad17)") (class "Default")
      (node (ref "J") (pin "17") (pinfunction "GND_17") (pintype "passive"))
    )
    (net (code "164") (name "unconnected-(J-GND-Pad18)") (class "Default")
      (node (ref "J") (pin "18") (pinfunction "GND_18") (pintype "passive"))
    )
    (net (code "165") (name "unconnected-(J-GND-Pad23)") (class "Default")
      (node (ref "J") (pin "23") (pinfunction "GND_23") (pintype "passive"))
    )
    (net (code "166") (name "unconnected-(J-GND-Pad24)") (class "Default")
      (node (ref "J") (pin "24") (pinfunction "GND_24") (pintype "passive"))
    )
    (net (code "167") (name "unconnected-(J-GND-Pad29)") (class "Default")
      (node (ref "J") (pin "29") (pinfunction "GND_29") (pintype "passive"))
    )
    (net (code "168") (name "unconnected-(J-GND-Pad30)") (class "Default")
      (node (ref "J") (pin "30") (pinfunction "GND_30") (pintype "passive"))
    )
    (net (code "169") (name "unconnected-(J-GND-Pad35)") (class "Default")
      (node (ref "J") (pin "35") (pinfunction "GND_35") (pintype "passive"))
    )
    (net (code "170") (name "unconnected-(J-GND-Pad36)") (class "Default")
      (node (ref "J") (pin "36") (pinfunction "GND_36") (pintype "passive"))
    )
    (net (code "171") (name "unconnected-(J-IO2-Pad2)") (class "Default")
      (node (ref "J") (pin "2") (pinfunction "IO2_2") (pintype "passive"))
    )
    (net (code "172") (name "unconnected-(J-NC-Pad1)") (class "Default")
      (node (ref "J") (pin "1") (pinfunction "NC_1") (pintype "passive"))
    )
  )
)
